# GabozeLite.net
KiCad netlist of a schematic drawn in EAGLE
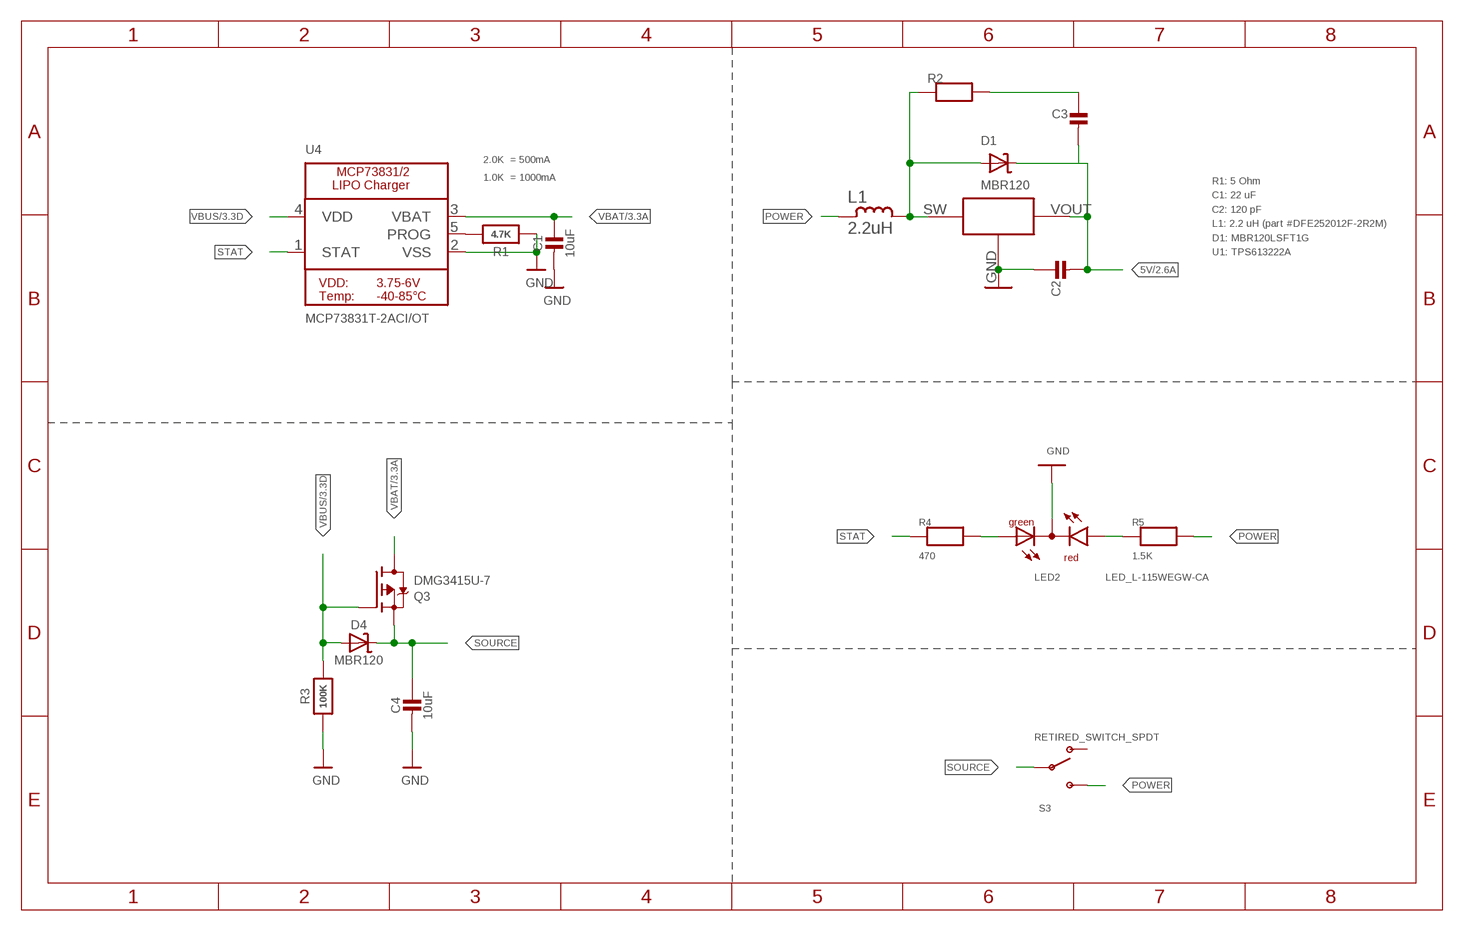
[diagram p0: schematic, sheet 1]
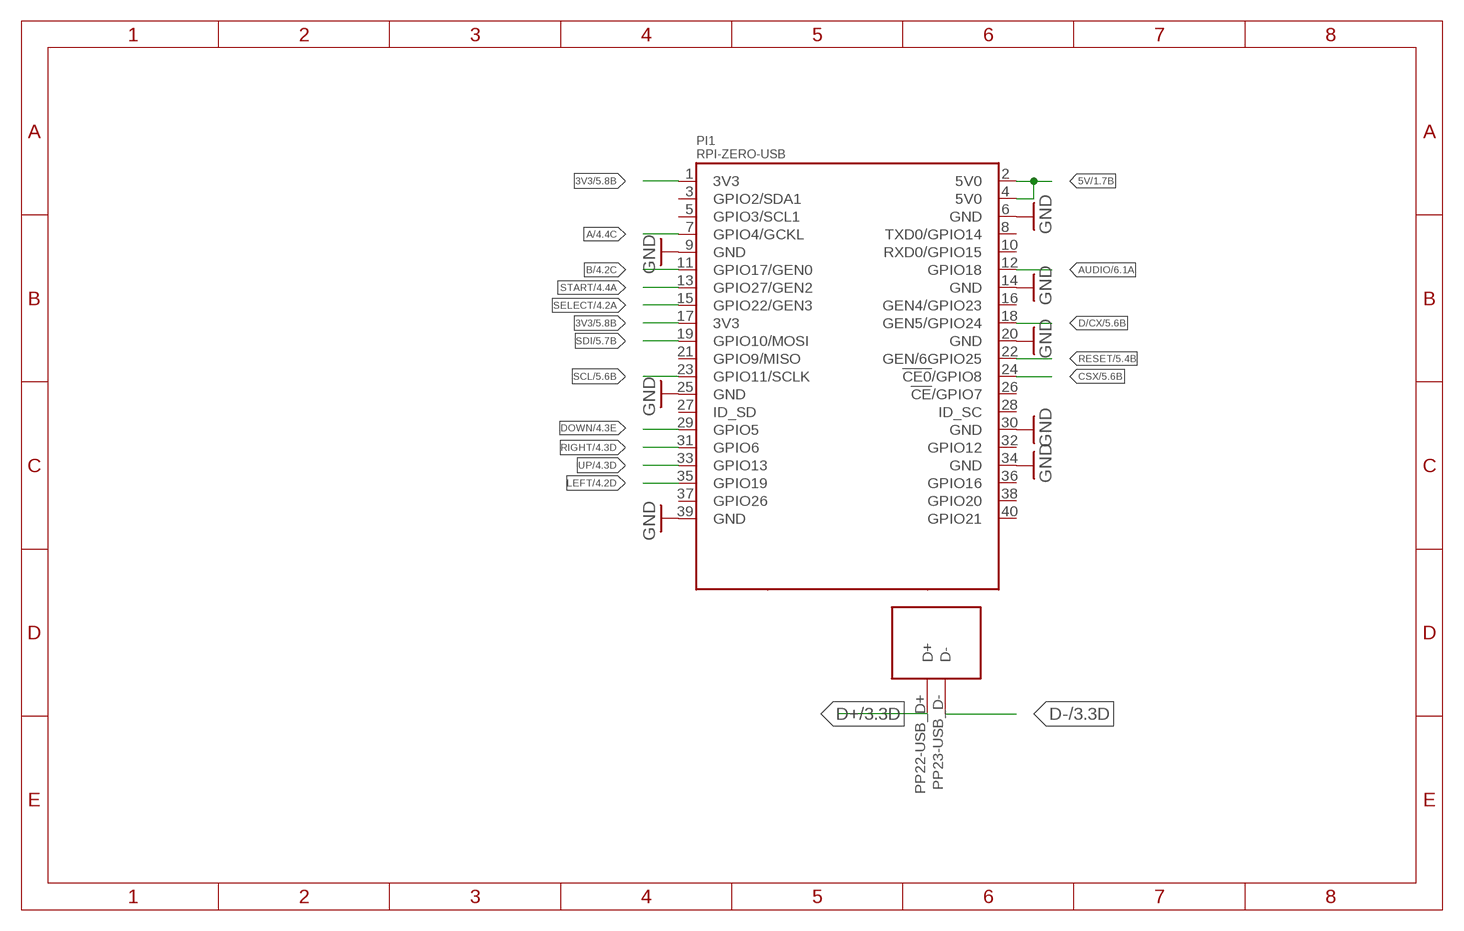
[diagram p1: schematic, sheet 2]
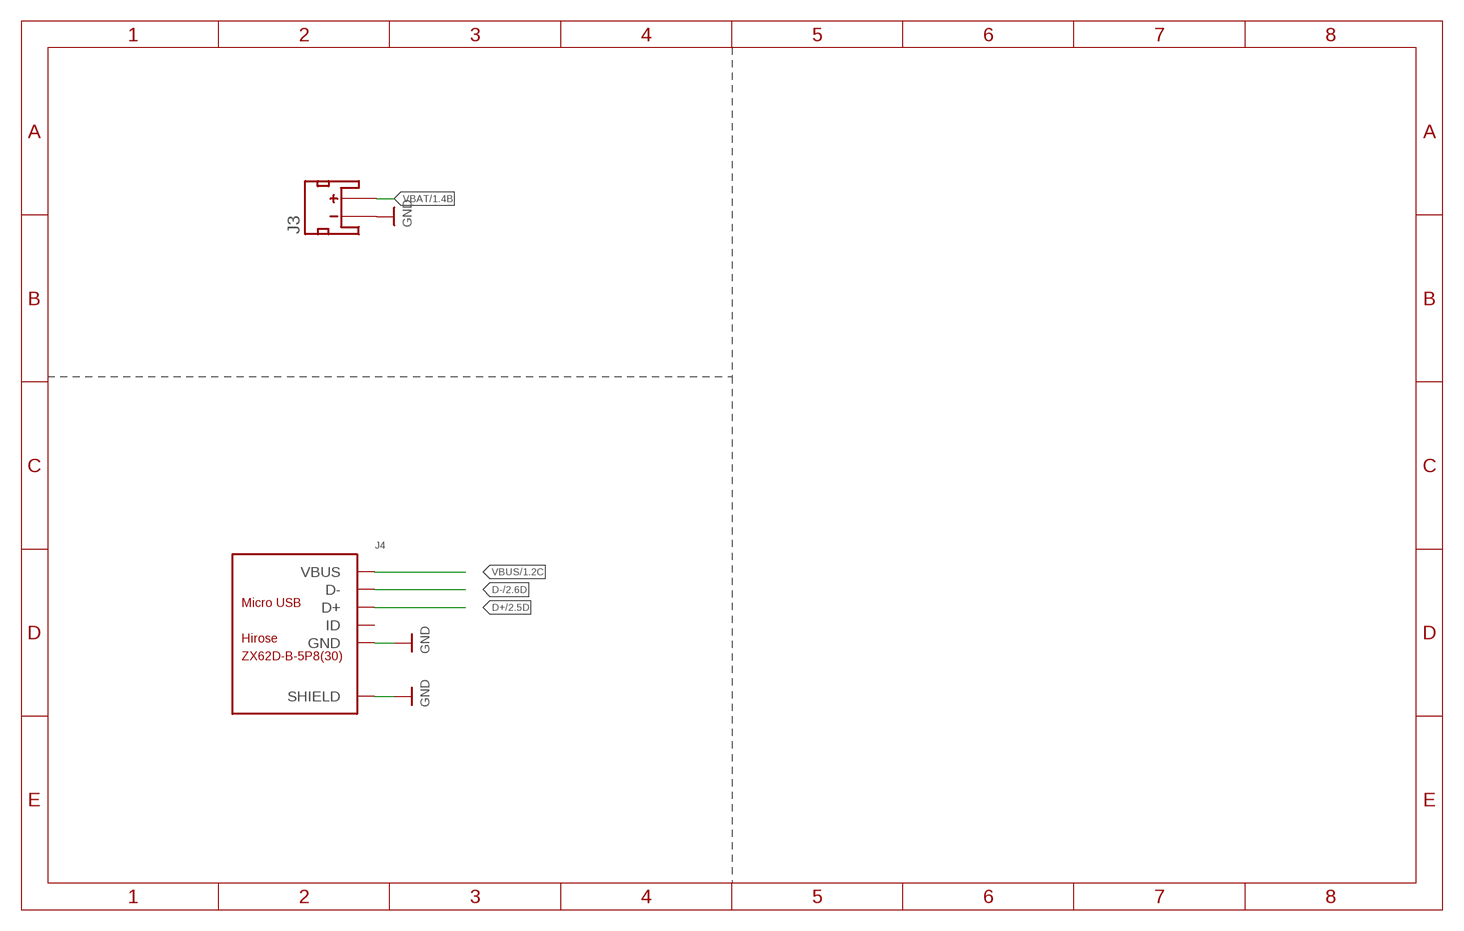
[diagram p2: schematic, sheet 3]
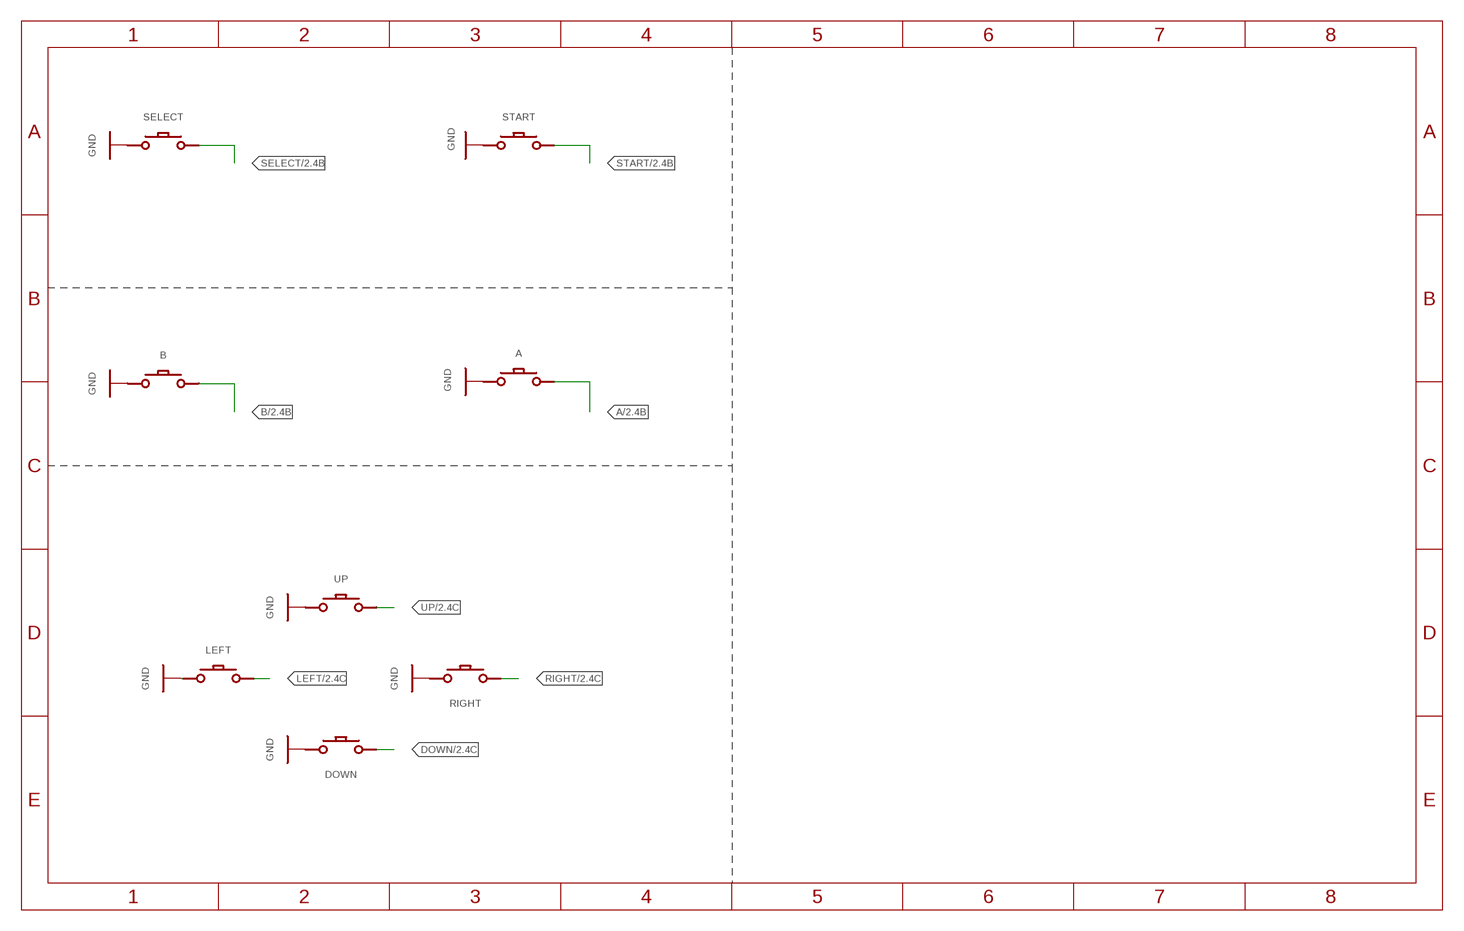
[diagram p3: schematic, sheet 4]
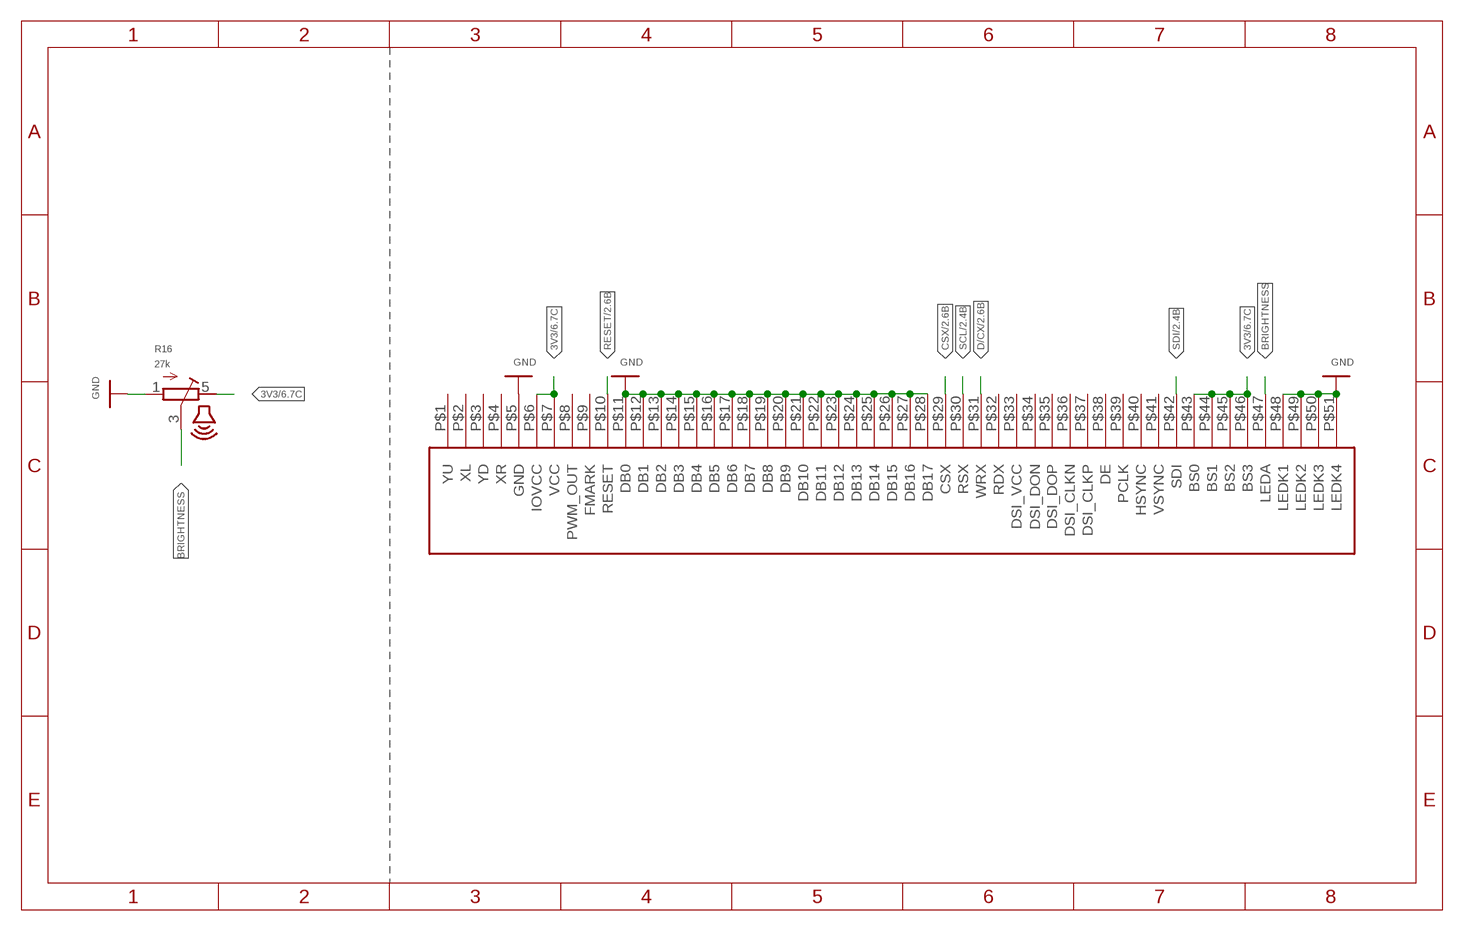
[diagram p4: schematic, sheet 5]
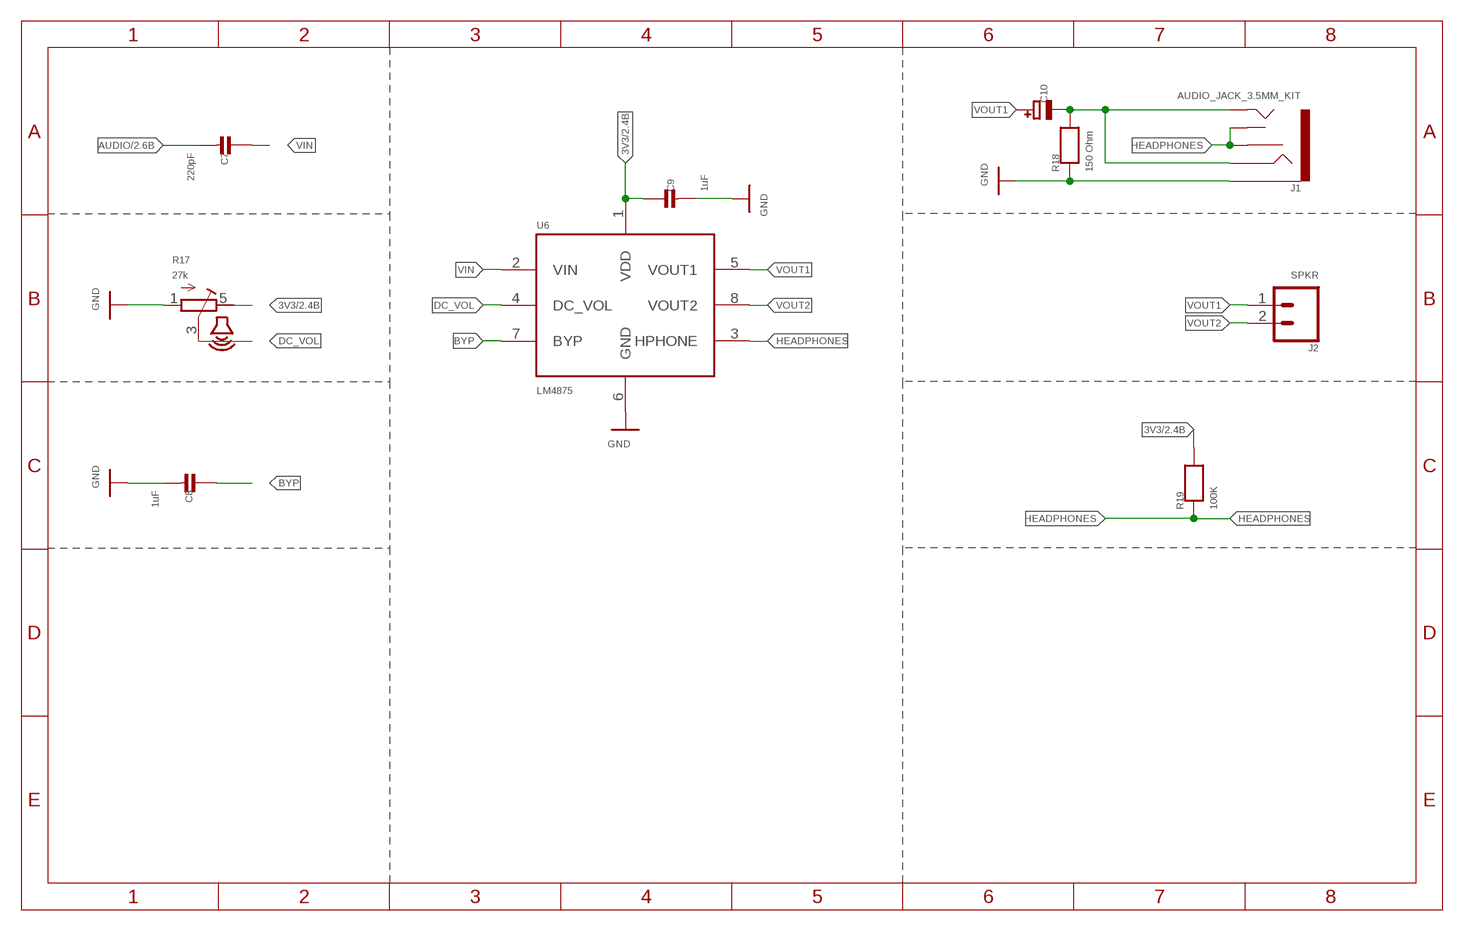
[diagram p5: schematic, sheet 6]
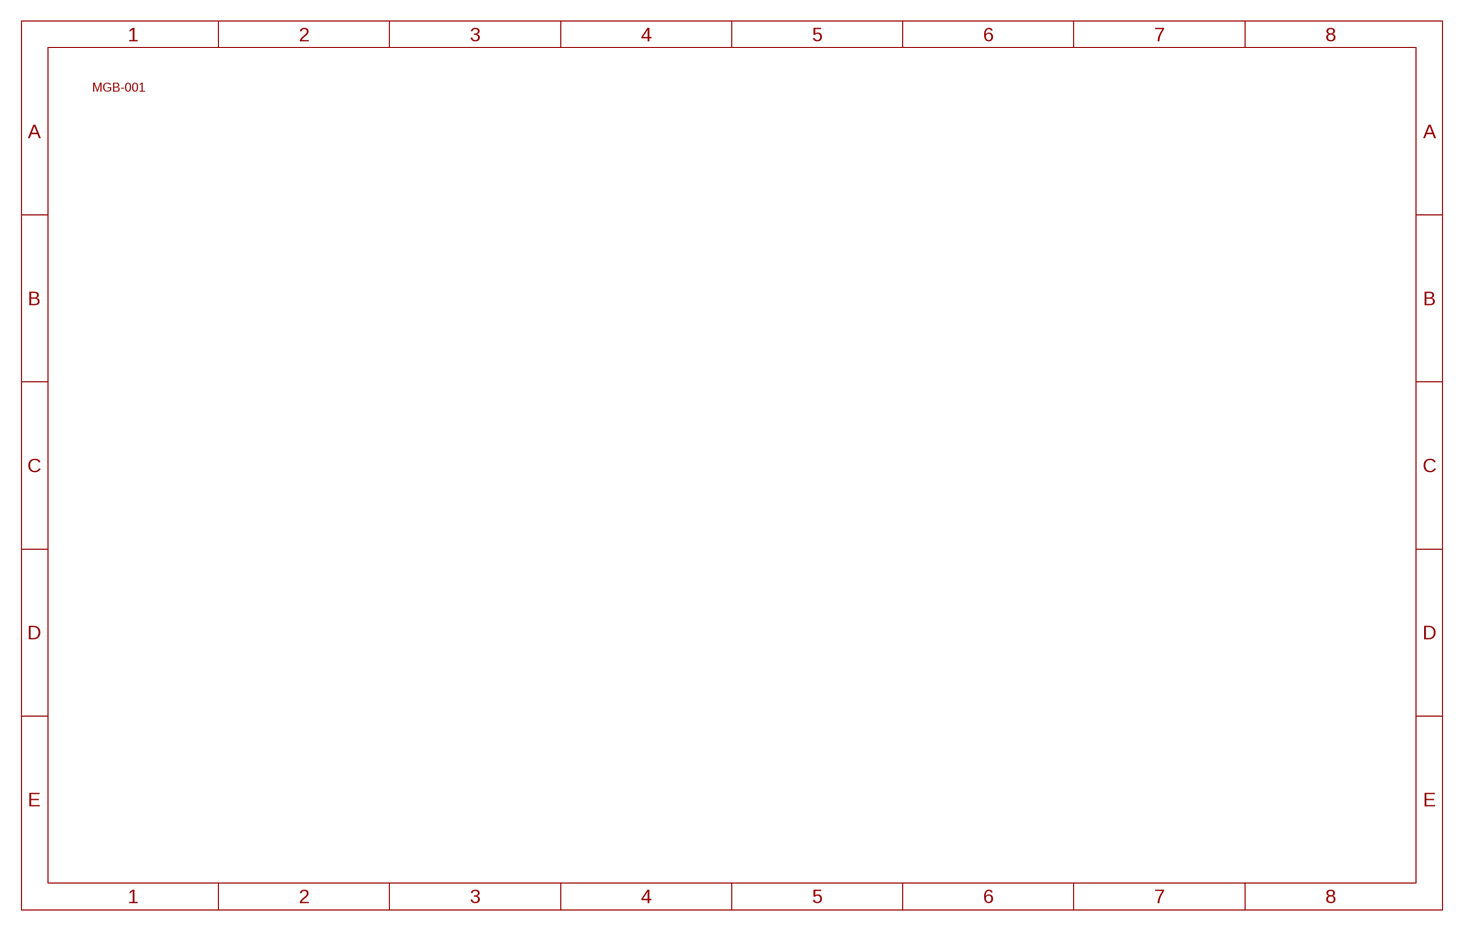
[diagram p6: schematic, sheet 7]

(export (version "E")
  (design (tool "Eeschema 10.0.6"))
  (components
    (comp (ref "C1")
      (value "10uF")
      (footprint "eagle-import:0603-MINI-CAP")
      (fields (field (name "MPN") "CL10A106MP8NNNC"))
      (libsource (lib "eagle-import") (part "CAP_CERAMIC"))
    )
    (comp (ref "C2")
      (value "22uf")
      (footprint "eagle-import:0603-MINI-CAP")
      (libsource (lib "eagle-import") (part "CAP_CERAMIC"))
    )
    (comp (ref "C3")
      (value "120pf")
      (footprint "eagle-import:0603-MINI-CAP")
      (libsource (lib "eagle-import") (part "CAP_CERAMIC"))
    )
    (comp (ref "C4")
      (value "10uF")
      (footprint "eagle-import:0603-MINI-CAP")
      (fields (field (name "MPN") "CL10A106MP8NNNC"))
      (libsource (lib "eagle-import") (part "CAP_CERAMIC"))
    )
    (comp (ref "D1")
      (value "MBR120")
      (footprint "eagle-import:SOD-123")
      (fields (field (name "MPN") "MBR120LSFT1G"))
      (libsource (lib "eagle-import") (part "DIODE-SCHOTTKYSOD-123"))
    )
    (comp (ref "D4")
      (value "MBR120")
      (footprint "eagle-import:SOD-123")
      (fields (field (name "MPN") "MBR120LSFT1G"))
      (libsource (lib "eagle-import") (part "DIODE-SCHOTTKYSOD-123"))
    )
    (comp (ref "L1")
      (value "2.2uH")
      (footprint "eagle-import:L1008CS")
      (libsource (lib "eagle-import") (part "L-1008CS"))
    )
    (comp (ref "LED2")
      (value "LED_L-115WEGW-CA")
      (footprint "eagle-import:LED_DUOLED-A-3MM")
      (fields (field (name "MPN") "SSL-LX3059IGW"))
      (libsource (lib "eagle-import") (part "LED_L-115WEGW-CA"))
    )
    (comp (ref "Q3")
      (value "DMG3415U-7")
      (footprint "eagle-import:SOT23-R")
      (libsource (lib "eagle-import") (part "MOSFET-P"))
    )
    (comp (ref "R1")
      (value "4.7K")
      (footprint "eagle-import:0603-MINI")
      (fields (field (name "MPN") "ERJ-PA3J472V"))
      (libsource (lib "eagle-import") (part "RESISTOR0603MINI"))
    )
    (comp (ref "R2")
      (value "5Ohm")
      (footprint "eagle-import:0603-MINI")
      (libsource (lib "eagle-import") (part "RESISTOR0603MINI"))
    )
    (comp (ref "R3")
      (value "100K")
      (footprint "eagle-import:0603-MINI")
      (fields (field (name "MPN") "ERJ-PA3J104V"))
      (libsource (lib "eagle-import") (part "RESISTOR0603MINI"))
    )
    (comp (ref "R4")
      (value "470")
      (footprint "eagle-import:0603-MINI")
      (fields (field (name "MPN") "ERJ-PA3J471V"))
      (libsource (lib "eagle-import") (part "RESISTOR0603MINI"))
    )
    (comp (ref "R5")
      (value "1.5K")
      (footprint "eagle-import:0603-MINI")
      (fields (field (name "MPN") "ERJ-PA3J152V"))
      (libsource (lib "eagle-import") (part "RESISTOR0603MINI"))
    )
    (comp (ref "S3")
      (value "RETIRED_SWITCH_SPDT")
      (footprint "eagle-import:RETIRED_KPS-1290")
      (fields (field (name "MPN") "RS-187R05A2-DS MT RT"))
      (libsource (lib "eagle-import") (part "RETIRED_SWITCH_SPDT"))
    )
    (comp (ref "U1")
      (value "TPS613222A")
      (footprint "eagle-import:TPS613222A")
      (libsource (lib "eagle-import") (part "TPS613222A"))
    )
    (comp (ref "U4")
      (value "MCP73831T-2ACI/OT")
      (footprint "eagle-import:SOT23-5-1")
      (libsource (lib "eagle-import") (part "MCP73831/2"))
    )
    (comp (ref "A")
      (value "CONDUCTIVE_BUTTONCONDUCTIVE_BUTTON_THICK")
      (footprint "eagle-import:CONDUCTIVE_BUTTON_THICK")
      (libsource (lib "eagle-import") (part "CONDUCTIVE_BUTTONCONDUCTIVE_BUTTON_THICK"))
    )
    (comp (ref "B")
      (value "CONDUCTIVE_BUTTONCONDUCTIVE_BUTTON_THICK")
      (footprint "eagle-import:CONDUCTIVE_BUTTON_THICK")
      (libsource (lib "eagle-import") (part "CONDUCTIVE_BUTTONCONDUCTIVE_BUTTON_THICK"))
    )
    (comp (ref "DOWN")
      (value "CONDUCTIVE_BUTTONCONDUCTIVE_BUTTON_DIRECTIONAL_THICK")
      (footprint "eagle-import:CONDUCTIVE_BUTTON_DIRECTIONAL_THICK")
      (libsource (lib "eagle-import") (part "CONDUCTIVE_BUTTONCONDUCTIVE_BUTTON_DIRECTIONAL_THICK"))
    )
    (comp (ref "LEFT")
      (value "CONDUCTIVE_BUTTONCONDUCTIVE_BUTTON_DIRECTIONAL_THICK")
      (footprint "eagle-import:CONDUCTIVE_BUTTON_DIRECTIONAL_THICK")
      (libsource (lib "eagle-import") (part "CONDUCTIVE_BUTTONCONDUCTIVE_BUTTON_DIRECTIONAL_THICK"))
    )
    (comp (ref "RIGHT")
      (value "CONDUCTIVE_BUTTONCONDUCTIVE_BUTTON_DIRECTIONAL_THICK")
      (footprint "eagle-import:CONDUCTIVE_BUTTON_DIRECTIONAL_THICK")
      (libsource (lib "eagle-import") (part "CONDUCTIVE_BUTTONCONDUCTIVE_BUTTON_DIRECTIONAL_THICK"))
    )
    (comp (ref "SELECT")
      (value "CONDUCTIVE_BUTTON_STARTSELECTCONDUCTIVE_BUTTON_THICK_STARTSELECT")
      (footprint "eagle-import:CONDUCTIVE_BUTTON_THICK_STARTSELECT")
      (libsource (lib "eagle-import") (part "CONDUCTIVE_BUTTON_STARTSELECTCONDUCTIVE_BUTTON_THICK_STARTSELECT"))
    )
    (comp (ref "START")
      (value "CONDUCTIVE_BUTTON_STARTSELECTCONDUCTIVE_BUTTON_THICK_STARTSELECT")
      (footprint "eagle-import:CONDUCTIVE_BUTTON_THICK_STARTSELECT")
      (libsource (lib "eagle-import") (part "CONDUCTIVE_BUTTON_STARTSELECTCONDUCTIVE_BUTTON_THICK_STARTSELECT"))
    )
    (comp (ref "UP")
      (value "CONDUCTIVE_BUTTONCONDUCTIVE_BUTTON_DIRECTIONAL_THICK")
      (footprint "eagle-import:CONDUCTIVE_BUTTON_DIRECTIONAL_THICK")
      (libsource (lib "eagle-import") (part "CONDUCTIVE_BUTTONCONDUCTIVE_BUTTON_DIRECTIONAL_THICK"))
    )
    (comp (ref "J3")
      (value "Batt Conn")
      (footprint "eagle-import:JST-2-SMD")
      (fields (field (name "MPN") "S2B-PH-SM4-TB(LF)(SN)"))
      (libsource (lib "eagle-import") (part "JST_2MM_MALE"))
    )
    (comp (ref "J4")
      (value "ZX62D-B-5P8(30)")
      (footprint "eagle-import:MICRO-USB5+6P-SMD-0.65-AB")
      (libsource (lib "eagle-import") (part "MICRO-USB-SMD(ZX62D-B-5P8(30))"))
    )
    (comp (ref "C7")
      (value "220pF")
      (footprint "eagle-import:0603-MINI-CAP")
      (fields (field (name "MPN") "CL10C221JB8NNNC"))
      (libsource (lib "eagle-import") (part "CAP_CERAMIC"))
    )
    (comp (ref "C8")
      (value "1uF")
      (footprint "eagle-import:0603-MINI-CAP")
      (fields (field (name "MPN") "CL10A105KP8NNNC"))
      (libsource (lib "eagle-import") (part "CAP_CERAMIC"))
    )
    (comp (ref "C9")
      (value "1uF")
      (footprint "eagle-import:0603-MINI-CAP")
      (fields (field (name "MPN") "CL10A105KP8NNNC"))
      (libsource (lib "eagle-import") (part "CAP_CERAMIC"))
    )
    (comp (ref "C10")
      (value "100uF")
      (footprint "eagle-import:EIA3216-18_A-W")
      (fields (field (name "MPN") "6TPH100MAEA"))
      (libsource (lib "eagle-import") (part "CAP_TANTALUMA/3216_WAVE"))
    )
    (comp (ref "J1")
      (value "AUDIO_JACK_3.5MM_KIT")
      (footprint "eagle-import:AUDIO-JACK-KIT")
      (fields (field (name "MPN") "SJ1-3525NG-GR"))
      (libsource (lib "eagle-import") (part "AUDIO_JACK_3.5MM_KIT"))
    )
    (comp (ref "J2")
      (value "SPKR")
      (footprint "eagle-import:1X02")
      (libsource (lib "eagle-import") (part "CONN_02"))
    )
    (comp (ref "R17")
      (value "27k")
      (footprint "eagle-import:THUMBWHEEL")
      (libsource (lib "eagle-import") (part "THUMBWHEEL"))
    )
    (comp (ref "R18")
      (value "150 Ohm")
      (footprint "eagle-import:0603-MINI")
      (fields (field (name "MPN") "ERJ-PA3J151V"))
      (libsource (lib "eagle-import") (part "RESISTOR0603MINI"))
    )
    (comp (ref "R19")
      (value "100K")
      (footprint "eagle-import:0603-MINI")
      (fields (field (name "MPN") "ERJ-PA3J104V"))
      (libsource (lib "eagle-import") (part "RESISTOR0603MINI"))
    )
    (comp (ref "U6")
      (value "LM4875")
      (footprint "eagle-import:SOIC8")
      (fields (field (name "MPN") "LM4875M/NOPB"))
      (libsource (lib "eagle-import") (part "LM4875"))
    )
    (comp (ref "R16")
      (value "27k")
      (footprint "eagle-import:THUMBWHEEL")
      (libsource (lib "eagle-import") (part "THUMBWHEEL"))
    )
    (comp (ref "U5")
      (value "ILI9342-2.6\"")
      (footprint "eagle-import:ILI9342-2.6_")
      (libsource (lib "eagle-import") (part "ILI9342-2.6{dblquote}"))
    )
    (comp (ref "U$1")
      (value "MGB-001")
      (footprint "eagle-import:MGB-001")
      (libsource (lib "eagle-import") (part "MGB-001"))
    )
    (comp (ref "PI1")
      (value "RPI-ZERO-USB")
      (footprint "eagle-import:RPI-ZERO-TH-USB-POGO")
      (libsource (lib "eagle-import") (part "RPI-ZERO-USB"))
    )
  )
  (nets
    (net (code "1") (name "3V3") (class "Default")
      (node (ref "C9") (pin "1") (pinfunction "1_1") (pintype "passive"))
      (node (ref "PI1") (pin "1") (pinfunction "3V3_1") (pintype "power_in"))
      (node (ref "PI1") (pin "17") (pinfunction "3V3_17") (pintype "power_in"))
      (node (ref "R16") (pin "5") (pinfunction "E_5") (pintype "passive"))
      (node (ref "R17") (pin "5") (pinfunction "E_5") (pintype "passive"))
      (node (ref "R19") (pin "2") (pinfunction "2_2") (pintype "passive"))
      (node (ref "U5") (pin "P$43") (pinfunction "BS0_P$43") (pintype "bidirectional"))
      (node (ref "U5") (pin "P$44") (pinfunction "BS1_P$44") (pintype "bidirectional"))
      (node (ref "U5") (pin "P$45") (pinfunction "BS2_P$45") (pintype "bidirectional"))
      (node (ref "U5") (pin "P$46") (pinfunction "BS3_P$46") (pintype "bidirectional"))
      (node (ref "U5") (pin "P$6") (pinfunction "IOVCC_P$6") (pintype "bidirectional"))
      (node (ref "U5") (pin "P$7") (pinfunction "VCC_P$7") (pintype "bidirectional"))
      (node (ref "U6") (pin "1") (pinfunction "VDD_1") (pintype "power_in"))
    )
    (net (code "2") (name "5V") (class "Default")
      (node (ref "C2") (pin "2") (pinfunction "2_2") (pintype "passive"))
      (node (ref "C3") (pin "2") (pinfunction "2_2") (pintype "passive"))
      (node (ref "D1") (pin "C") (pinfunction "C_C") (pintype "passive"))
      (node (ref "PI1") (pin "2") (pinfunction "5V0_2") (pintype "power_in"))
      (node (ref "PI1") (pin "4") (pinfunction "5V0_4") (pintype "power_in"))
      (node (ref "U1") (pin "VOUT") (pinfunction "VOUT_VOUT") (pintype "bidirectional"))
    )
    (net (code "3") (name "A") (class "Default")
      (node (ref "A") (pin "P$ACTIVE") (pinfunction "P$ACTIVE_P$ACTIVE") (pintype "bidirectional"))
      (node (ref "PI1") (pin "7") (pinfunction "GPIO4/GCKL_7") (pintype "bidirectional"))
    )
    (net (code "4") (name "AUDIO") (class "Default")
      (node (ref "C7") (pin "2") (pinfunction "2_2") (pintype "passive"))
      (node (ref "PI1") (pin "12") (pinfunction "GPIO18_12") (pintype "bidirectional"))
    )
    (net (code "5") (name "B") (class "Default")
      (node (ref "B") (pin "P$ACTIVE") (pinfunction "P$ACTIVE_P$ACTIVE") (pintype "bidirectional"))
      (node (ref "PI1") (pin "11") (pinfunction "GPIO17/GEN0_11") (pintype "bidirectional"))
    )
    (net (code "6") (name "BRIGHTNESS") (class "Default")
      (node (ref "R16") (pin "3") (pinfunction "S_3") (pintype "passive"))
      (node (ref "U5") (pin "P$47") (pinfunction "LEDA_P$47") (pintype "bidirectional"))
    )
    (net (code "7") (name "BYP") (class "Default")
      (node (ref "C8") (pin "1") (pinfunction "1_1") (pintype "passive"))
      (node (ref "U6") (pin "7") (pinfunction "BYP_7") (pintype "bidirectional"))
    )
    (net (code "8") (name "CSX") (class "Default")
      (node (ref "PI1") (pin "24") (pinfunction "~{CE0}/GPIO8_24") (pintype "bidirectional"))
      (node (ref "U5") (pin "P$29") (pinfunction "CSX_P$29") (pintype "bidirectional"))
    )
    (net (code "9") (name "D+") (class "Default")
      (node (ref "J4") (pin "3") (pinfunction "D+_3") (pintype "bidirectional"))
      (node (ref "PI1") (pin "PP22-USB_D+") (pinfunction "D+_PP22-USB_D+") (pintype "bidirectional"))
    )
    (net (code "10") (name "D-") (class "Default")
      (node (ref "J4") (pin "2") (pinfunction "D-_2") (pintype "bidirectional"))
      (node (ref "PI1") (pin "PP23-USB_D-") (pinfunction "D-_PP23-USB_D-") (pintype "bidirectional"))
    )
    (net (code "11") (name "DC_VOL") (class "Default")
      (node (ref "R17") (pin "3") (pinfunction "S_3") (pintype "passive"))
      (node (ref "U6") (pin "4") (pinfunction "DC_VOL_4") (pintype "input"))
    )
    (net (code "12") (name "DOWN") (class "Default")
      (node (ref "DOWN") (pin "P$ACTIVE") (pinfunction "P$ACTIVE_P$ACTIVE") (pintype "bidirectional"))
      (node (ref "PI1") (pin "29") (pinfunction "GPIO5_29") (pintype "bidirectional"))
    )
    (net (code "13") (name "D{slash}CX") (class "Default")
      (node (ref "PI1") (pin "18") (pinfunction "GEN5/GPIO24_18") (pintype "bidirectional"))
      (node (ref "U5") (pin "P$31") (pinfunction "WRX_P$31") (pintype "bidirectional"))
    )
    (net (code "14") (name "GND") (class "Default")
      (node (ref "A") (pin "P$GND") (pinfunction "P$GND_P$GND") (pintype "bidirectional"))
      (node (ref "B") (pin "P$GND") (pinfunction "P$GND_P$GND") (pintype "bidirectional"))
      (node (ref "C1") (pin "2") (pinfunction "2_2") (pintype "passive"))
      (node (ref "C2") (pin "1") (pinfunction "1_1") (pintype "passive"))
      (node (ref "C4") (pin "2") (pinfunction "2_2") (pintype "passive"))
      (node (ref "C8") (pin "2") (pinfunction "2_2") (pintype "passive"))
      (node (ref "C9") (pin "2") (pinfunction "2_2") (pintype "passive"))
      (node (ref "DOWN") (pin "P$GND") (pinfunction "P$GND_P$GND") (pintype "bidirectional"))
      (node (ref "J1") (pin "SLEEVE") (pinfunction "SLEEVE_SLEEVE") (pintype "bidirectional"))
      (node (ref "J3") (pin "1") (pinfunction "-_1") (pintype "bidirectional"))
      (node (ref "J4") (pin "5") (pinfunction "GND_5") (pintype "power_in"))
      (node (ref "J4") (pin "P1") (pinfunction "SHIELD_P1") (pintype "power_in"))
      (node (ref "J4") (pin "P2") (pinfunction "SHIELD_P2") (pintype "power_in"))
      (node (ref "J4") (pin "P3") (pinfunction "SHIELD_P3") (pintype "power_in"))
      (node (ref "J4") (pin "P4") (pinfunction "SHIELD_P4") (pintype "power_in"))
      (node (ref "J4") (pin "P5") (pinfunction "SHIELD_P5") (pintype "power_in"))
      (node (ref "J4") (pin "P6") (pinfunction "SHIELD_P6") (pintype "power_in"))
      (node (ref "LED2") (pin "2") (pinfunction "A_2") (pintype "passive"))
      (node (ref "LEFT") (pin "P$GND") (pinfunction "P$GND_P$GND") (pintype "bidirectional"))
      (node (ref "PI1") (pin "14") (pinfunction "GND_14") (pintype "power_in"))
      (node (ref "PI1") (pin "20") (pinfunction "GND_20") (pintype "power_in"))
      (node (ref "PI1") (pin "25") (pinfunction "GND_25") (pintype "power_in"))
      (node (ref "PI1") (pin "30") (pinfunction "GND_30") (pintype "power_in"))
      (node (ref "PI1") (pin "34") (pinfunction "GND_34") (pintype "power_in"))
      (node (ref "PI1") (pin "39") (pinfunction "GND_39") (pintype "power_in"))
      (node (ref "PI1") (pin "6") (pinfunction "GND_6") (pintype "power_in"))
      (node (ref "PI1") (pin "9") (pinfunction "GND_9") (pintype "power_in"))
      (node (ref "R1") (pin "1") (pinfunction "1_1") (pintype "passive"))
      (node (ref "R16") (pin "1") (pinfunction "A_1") (pintype "passive"))
      (node (ref "R17") (pin "1") (pinfunction "A_1") (pintype "passive"))
      (node (ref "R18") (pin "1") (pinfunction "1_1") (pintype "passive"))
      (node (ref "R3") (pin "1") (pinfunction "1_1") (pintype "passive"))
      (node (ref "RIGHT") (pin "P$GND") (pinfunction "P$GND_P$GND") (pintype "bidirectional"))
      (node (ref "SELECT") (pin "P$GND") (pinfunction "P$GND_P$GND") (pintype "bidirectional"))
      (node (ref "SELECT") (pin "P$GND1") (pinfunction "P$GND_P$GND1") (pintype "bidirectional"))
      (node (ref "SELECT") (pin "P$GND2") (pinfunction "P$GND_P$GND2") (pintype "bidirectional"))
      (node (ref "SELECT") (pin "P$GND3") (pinfunction "P$GND_P$GND3") (pintype "bidirectional"))
      (node (ref "START") (pin "P$GND") (pinfunction "P$GND_P$GND") (pintype "bidirectional"))
      (node (ref "START") (pin "P$GND1") (pinfunction "P$GND_P$GND1") (pintype "bidirectional"))
      (node (ref "START") (pin "P$GND2") (pinfunction "P$GND_P$GND2") (pintype "bidirectional"))
      (node (ref "START") (pin "P$GND3") (pinfunction "P$GND_P$GND3") (pintype "bidirectional"))
      (node (ref "U1") (pin "GND") (pinfunction "GND_GND") (pintype "bidirectional"))
      (node (ref "U4") (pin "2") (pinfunction "VSS_2") (pintype "power_in"))
      (node (ref "U5") (pin "P$11") (pinfunction "DB0_P$11") (pintype "bidirectional"))
      (node (ref "U5") (pin "P$12") (pinfunction "DB1_P$12") (pintype "bidirectional"))
      (node (ref "U5") (pin "P$13") (pinfunction "DB2_P$13") (pintype "bidirectional"))
      (node (ref "U5") (pin "P$14") (pinfunction "DB3_P$14") (pintype "bidirectional"))
      (node (ref "U5") (pin "P$15") (pinfunction "DB4_P$15") (pintype "bidirectional"))
      (node (ref "U5") (pin "P$16") (pinfunction "DB5_P$16") (pintype "bidirectional"))
      (node (ref "U5") (pin "P$17") (pinfunction "DB6_P$17") (pintype "bidirectional"))
      (node (ref "U5") (pin "P$18") (pinfunction "DB7_P$18") (pintype "bidirectional"))
      (node (ref "U5") (pin "P$19") (pinfunction "DB8_P$19") (pintype "bidirectional"))
      (node (ref "U5") (pin "P$20") (pinfunction "DB9_P$20") (pintype "bidirectional"))
      (node (ref "U5") (pin "P$21") (pinfunction "DB10_P$21") (pintype "bidirectional"))
      (node (ref "U5") (pin "P$22") (pinfunction "DB11_P$22") (pintype "bidirectional"))
      (node (ref "U5") (pin "P$23") (pinfunction "DB12_P$23") (pintype "bidirectional"))
      (node (ref "U5") (pin "P$24") (pinfunction "DB13_P$24") (pintype "bidirectional"))
      (node (ref "U5") (pin "P$25") (pinfunction "DB14_P$25") (pintype "bidirectional"))
      (node (ref "U5") (pin "P$26") (pinfunction "DB15_P$26") (pintype "bidirectional"))
      (node (ref "U5") (pin "P$27") (pinfunction "DB16_P$27") (pintype "bidirectional"))
      (node (ref "U5") (pin "P$28") (pinfunction "DB17_P$28") (pintype "bidirectional"))
      (node (ref "U5") (pin "P$48") (pinfunction "LEDK1_P$48") (pintype "bidirectional"))
      (node (ref "U5") (pin "P$49") (pinfunction "LEDK2_P$49") (pintype "bidirectional"))
      (node (ref "U5") (pin "P$5") (pinfunction "GND_P$5") (pintype "bidirectional"))
      (node (ref "U5") (pin "P$50") (pinfunction "LEDK3_P$50") (pintype "bidirectional"))
      (node (ref "U5") (pin "P$51") (pinfunction "LEDK4_P$51") (pintype "bidirectional"))
      (node (ref "U6") (pin "6") (pinfunction "GND_6") (pintype "power_in"))
      (node (ref "UP") (pin "P$GND") (pinfunction "P$GND_P$GND") (pintype "bidirectional"))
    )
    (net (code "15") (name "HEADPHONES") (class "Default")
      (node (ref "J1") (pin "RSH") (pinfunction "RSH_RSH") (pintype "bidirectional"))
      (node (ref "J1") (pin "TSH") (pinfunction "TSH_TSH") (pintype "bidirectional"))
      (node (ref "R19") (pin "1") (pinfunction "1_1") (pintype "passive"))
      (node (ref "U6") (pin "3") (pinfunction "HPHONE_3") (pintype "input"))
    )
    (net (code "16") (name "LEFT") (class "Default")
      (node (ref "LEFT") (pin "P$ACTIVE") (pinfunction "P$ACTIVE_P$ACTIVE") (pintype "bidirectional"))
      (node (ref "PI1") (pin "35") (pinfunction "GPIO19_35") (pintype "bidirectional"))
    )
    (net (code "17") (name "Net-(C3-Pad1)") (class "Default")
      (node (ref "C3") (pin "1") (pinfunction "1_1") (pintype "passive"))
      (node (ref "R2") (pin "2") (pinfunction "2_2") (pintype "passive"))
    )
    (net (code "18") (name "Net-(C10-Pad-)") (class "Default")
      (node (ref "C10") (pin "-") (pinfunction "-_-") (pintype "passive"))
      (node (ref "J1") (pin "RING") (pinfunction "RING_RING") (pintype "bidirectional"))
      (node (ref "J1") (pin "TIP") (pinfunction "TIP_TIP") (pintype "bidirectional"))
      (node (ref "R18") (pin "2") (pinfunction "2_2") (pintype "passive"))
    )
    (net (code "19") (name "Net-(L1-P$2)") (class "Default")
      (node (ref "D1") (pin "A") (pinfunction "A_A") (pintype "passive"))
      (node (ref "L1") (pin "2") (pinfunction "P$2_2") (pintype "passive"))
      (node (ref "R2") (pin "1") (pinfunction "1_1") (pintype "passive"))
      (node (ref "U1") (pin "SW") (pinfunction "SW_SW") (pintype "bidirectional"))
    )
    (net (code "20") (name "Net-(LED2-CG)") (class "Default")
      (node (ref "LED2") (pin "1") (pinfunction "CG_1") (pintype "passive"))
      (node (ref "R4") (pin "2") (pinfunction "2_2") (pintype "passive"))
    )
    (net (code "21") (name "Net-(LED2-CR)") (class "Default")
      (node (ref "LED2") (pin "3") (pinfunction "CR_3") (pintype "passive"))
      (node (ref "R5") (pin "1") (pinfunction "1_1") (pintype "passive"))
    )
    (net (code "22") (name "Net-(U4-PROG)") (class "Default")
      (node (ref "R1") (pin "2") (pinfunction "2_2") (pintype "passive"))
      (node (ref "U4") (pin "5") (pinfunction "PROG_5") (pintype "input"))
    )
    (net (code "23") (name "POWER") (class "Default")
      (node (ref "L1") (pin "1") (pinfunction "P$1_1") (pintype "passive"))
      (node (ref "R5") (pin "2") (pinfunction "2_2") (pintype "passive"))
      (node (ref "S3") (pin "S") (pinfunction "S_S") (pintype "passive"))
    )
    (net (code "24") (name "RESET") (class "Default")
      (node (ref "PI1") (pin "22") (pinfunction "GEN/6GPIO25_22") (pintype "bidirectional"))
      (node (ref "U5") (pin "P$10") (pinfunction "RESET_P$10") (pintype "bidirectional"))
    )
    (net (code "25") (name "RIGHT") (class "Default")
      (node (ref "PI1") (pin "31") (pinfunction "GPIO6_31") (pintype "bidirectional"))
      (node (ref "RIGHT") (pin "P$ACTIVE") (pinfunction "P$ACTIVE_P$ACTIVE") (pintype "bidirectional"))
    )
    (net (code "26") (name "SCL") (class "Default")
      (node (ref "PI1") (pin "23") (pinfunction "GPIO11/SCLK_23") (pintype "bidirectional"))
      (node (ref "U5") (pin "P$30") (pinfunction "RSX_P$30") (pintype "bidirectional"))
    )
    (net (code "27") (name "SDI") (class "Default")
      (node (ref "PI1") (pin "19") (pinfunction "GPIO10/MOSI_19") (pintype "bidirectional"))
      (node (ref "U5") (pin "P$42") (pinfunction "SDI_P$42") (pintype "bidirectional"))
    )
    (net (code "28") (name "SELECT") (class "Default")
      (node (ref "PI1") (pin "15") (pinfunction "GPIO22/GEN3_15") (pintype "bidirectional"))
      (node (ref "SELECT") (pin "P$ACTIVE") (pinfunction "P$ACTIVE_P$ACTIVE") (pintype "bidirectional"))
      (node (ref "SELECT") (pin "P$ACTIVE1") (pinfunction "P$ACTIVE_P$ACTIVE1") (pintype "bidirectional"))
      (node (ref "SELECT") (pin "P$ACTIVE2") (pinfunction "P$ACTIVE_P$ACTIVE2") (pintype "bidirectional"))
      (node (ref "SELECT") (pin "P$ACTIVE3") (pinfunction "P$ACTIVE_P$ACTIVE3") (pintype "bidirectional"))
      (node (ref "SELECT") (pin "P$ACTIVE4") (pinfunction "P$ACTIVE_P$ACTIVE4") (pintype "bidirectional"))
      (node (ref "SELECT") (pin "P$ACTIVE5") (pinfunction "P$ACTIVE_P$ACTIVE5") (pintype "bidirectional"))
      (node (ref "SELECT") (pin "P$ACTIVE6") (pinfunction "P$ACTIVE_P$ACTIVE6") (pintype "bidirectional"))
    )
    (net (code "29") (name "SOURCE") (class "Default")
      (node (ref "C4") (pin "1") (pinfunction "1_1") (pintype "passive"))
      (node (ref "D4") (pin "C") (pinfunction "C_C") (pintype "passive"))
      (node (ref "Q3") (pin "2") (pinfunction "S_2") (pintype "passive"))
      (node (ref "S3") (pin "P") (pinfunction "P_P") (pintype "passive"))
    )
    (net (code "30") (name "START") (class "Default")
      (node (ref "PI1") (pin "13") (pinfunction "GPIO27/GEN2_13") (pintype "bidirectional"))
      (node (ref "START") (pin "P$ACTIVE") (pinfunction "P$ACTIVE_P$ACTIVE") (pintype "bidirectional"))
      (node (ref "START") (pin "P$ACTIVE1") (pinfunction "P$ACTIVE_P$ACTIVE1") (pintype "bidirectional"))
      (node (ref "START") (pin "P$ACTIVE2") (pinfunction "P$ACTIVE_P$ACTIVE2") (pintype "bidirectional"))
      (node (ref "START") (pin "P$ACTIVE3") (pinfunction "P$ACTIVE_P$ACTIVE3") (pintype "bidirectional"))
      (node (ref "START") (pin "P$ACTIVE4") (pinfunction "P$ACTIVE_P$ACTIVE4") (pintype "bidirectional"))
      (node (ref "START") (pin "P$ACTIVE5") (pinfunction "P$ACTIVE_P$ACTIVE5") (pintype "bidirectional"))
      (node (ref "START") (pin "P$ACTIVE6") (pinfunction "P$ACTIVE_P$ACTIVE6") (pintype "bidirectional"))
    )
    (net (code "31") (name "STAT") (class "Default")
      (node (ref "R4") (pin "1") (pinfunction "1_1") (pintype "passive"))
      (node (ref "U4") (pin "1") (pinfunction "STAT_1") (pintype "output"))
    )
    (net (code "32") (name "UP") (class "Default")
      (node (ref "PI1") (pin "33") (pinfunction "GPIO13_33") (pintype "bidirectional"))
      (node (ref "UP") (pin "P$ACTIVE") (pinfunction "P$ACTIVE_P$ACTIVE") (pintype "bidirectional"))
    )
    (net (code "33") (name "VBAT") (class "Default")
      (node (ref "C1") (pin "1") (pinfunction "1_1") (pintype "passive"))
      (node (ref "J3") (pin "2") (pinfunction "+_2") (pintype "bidirectional"))
      (node (ref "Q3") (pin "3") (pinfunction "D_3") (pintype "passive"))
      (node (ref "U4") (pin "3") (pinfunction "VBAT_3") (pintype "power_in"))
    )
    (net (code "34") (name "VBUS") (class "Default")
      (node (ref "D4") (pin "A") (pinfunction "A_A") (pintype "passive"))
      (node (ref "J4") (pin "1") (pinfunction "VBUS_1") (pintype "power_in"))
      (node (ref "Q3") (pin "1") (pinfunction "G_1") (pintype "passive"))
      (node (ref "R3") (pin "2") (pinfunction "2_2") (pintype "passive"))
      (node (ref "U4") (pin "4") (pinfunction "VDD_4") (pintype "power_in"))
    )
    (net (code "35") (name "VIN") (class "Default")
      (node (ref "C7") (pin "1") (pinfunction "1_1") (pintype "passive"))
      (node (ref "U6") (pin "2") (pinfunction "VIN_2") (pintype "input"))
    )
    (net (code "36") (name "VOUT1") (class "Default")
      (node (ref "C10") (pin "+") (pinfunction "+_+") (pintype "passive"))
      (node (ref "J2") (pin "1") (pinfunction "1_1") (pintype "passive"))
      (node (ref "U6") (pin "5") (pinfunction "VOUT1_5") (pintype "output"))
    )
    (net (code "37") (name "VOUT2") (class "Default")
      (node (ref "J2") (pin "2") (pinfunction "2_2") (pintype "passive"))
      (node (ref "U6") (pin "8") (pinfunction "VOUT2_8") (pintype "output"))
    )
    (net (code "38") (name "unconnected-(J3-PAD1-PadNC1)") (class "Default")
      (node (ref "J3") (pin "NC1") (pinfunction "PAD1_NC1") (pintype "bidirectional"))
    )
    (net (code "39") (name "unconnected-(J3-PAD2-PadNC2)") (class "Default")
      (node (ref "J3") (pin "NC2") (pinfunction "PAD2_NC2") (pintype "bidirectional"))
    )
    (net (code "40") (name "unconnected-(J4-ID-Pad4)") (class "Default")
      (node (ref "J4") (pin "4") (pinfunction "ID_4") (pintype "bidirectional"))
    )
    (net (code "41") (name "unconnected-(PI1-GEN4{slash}GPIO23-Pad16)") (class "Default")
      (node (ref "PI1") (pin "16") (pinfunction "GEN4/GPIO23_16") (pintype "bidirectional"))
    )
    (net (code "42") (name "unconnected-(PI1-GPIO2{slash}SDA1-Pad3)") (class "Default")
      (node (ref "PI1") (pin "3") (pinfunction "GPIO2/SDA1_3") (pintype "bidirectional"))
    )
    (net (code "43") (name "unconnected-(PI1-GPIO3{slash}SCL1-Pad5)") (class "Default")
      (node (ref "PI1") (pin "5") (pinfunction "GPIO3/SCL1_5") (pintype "bidirectional"))
    )
    (net (code "44") (name "unconnected-(PI1-GPIO9{slash}MISO-Pad21)") (class "Default")
      (node (ref "PI1") (pin "21") (pinfunction "GPIO9/MISO_21") (pintype "bidirectional"))
    )
    (net (code "45") (name "unconnected-(PI1-GPIO12-Pad32)") (class "Default")
      (node (ref "PI1") (pin "32") (pinfunction "GPIO12_32") (pintype "bidirectional"))
    )
    (net (code "46") (name "unconnected-(PI1-GPIO16-Pad36)") (class "Default")
      (node (ref "PI1") (pin "36") (pinfunction "GPIO16_36") (pintype "bidirectional"))
    )
    (net (code "47") (name "unconnected-(PI1-GPIO20-Pad38)") (class "Default")
      (node (ref "PI1") (pin "38") (pinfunction "GPIO20_38") (pintype "bidirectional"))
    )
    (net (code "48") (name "unconnected-(PI1-GPIO21-Pad40)") (class "Default")
      (node (ref "PI1") (pin "40") (pinfunction "GPIO21_40") (pintype "bidirectional"))
    )
    (net (code "49") (name "unconnected-(PI1-GPIO26-Pad37)") (class "Default")
      (node (ref "PI1") (pin "37") (pinfunction "GPIO26_37") (pintype "bidirectional"))
    )
    (net (code "50") (name "unconnected-(PI1-ID_SC-Pad28)") (class "Default")
      (node (ref "PI1") (pin "28") (pinfunction "ID_SC_28") (pintype "bidirectional"))
    )
    (net (code "51") (name "unconnected-(PI1-ID_SD-Pad27)") (class "Default")
      (node (ref "PI1") (pin "27") (pinfunction "ID_SD_27") (pintype "bidirectional"))
    )
    (net (code "52") (name "unconnected-(PI1-RXD0{slash}GPIO15-Pad10)") (class "Default")
      (node (ref "PI1") (pin "10") (pinfunction "RXD0/GPIO15_10") (pintype "bidirectional"))
    )
    (net (code "53") (name "unconnected-(PI1-TXD0{slash}GPIO14-Pad8)") (class "Default")
      (node (ref "PI1") (pin "8") (pinfunction "TXD0/GPIO14_8") (pintype "bidirectional"))
    )
    (net (code "54") (name "unconnected-(PI1-~{CE}{slash}GPIO7-Pad26)") (class "Default")
      (node (ref "PI1") (pin "26") (pinfunction "~{CE}/GPIO7_26") (pintype "bidirectional"))
    )
    (net (code "55") (name "unconnected-(S3-PadO)") (class "Default")
      (node (ref "S3") (pin "O") (pinfunction "O_O") (pintype "passive"))
    )
    (net (code "56") (name "unconnected-(U5-DE-PadP$38)") (class "Default")
      (node (ref "U5") (pin "P$38") (pinfunction "DE_P$38") (pintype "bidirectional"))
    )
    (net (code "57") (name "unconnected-(U5-DSI_CLKN-PadP$36)") (class "Default")
      (node (ref "U5") (pin "P$36") (pinfunction "DSI_CLKN_P$36") (pintype "bidirectional"))
    )
    (net (code "58") (name "unconnected-(U5-DSI_CLKP-PadP$37)") (class "Default")
      (node (ref "U5") (pin "P$37") (pinfunction "DSI_CLKP_P$37") (pintype "bidirectional"))
    )
    (net (code "59") (name "unconnected-(U5-DSI_DON-PadP$34)") (class "Default")
      (node (ref "U5") (pin "P$34") (pinfunction "DSI_DON_P$34") (pintype "bidirectional"))
    )
    (net (code "60") (name "unconnected-(U5-DSI_DOP-PadP$35)") (class "Default")
      (node (ref "U5") (pin "P$35") (pinfunction "DSI_DOP_P$35") (pintype "bidirectional"))
    )
    (net (code "61") (name "unconnected-(U5-DSI_VCC-PadP$33)") (class "Default")
      (node (ref "U5") (pin "P$33") (pinfunction "DSI_VCC_P$33") (pintype "bidirectional"))
    )
    (net (code "62") (name "unconnected-(U5-FMARK-PadP$9)") (class "Default")
      (node (ref "U5") (pin "P$9") (pinfunction "FMARK_P$9") (pintype "bidirectional"))
    )
    (net (code "63") (name "unconnected-(U5-HSYNC-PadP$40)") (class "Default")
      (node (ref "U5") (pin "P$40") (pinfunction "HSYNC_P$40") (pintype "bidirectional"))
    )
    (net (code "64") (name "unconnected-(U5-PCLK-PadP$39)") (class "Default")
      (node (ref "U5") (pin "P$39") (pinfunction "PCLK_P$39") (pintype "bidirectional"))
    )
    (net (code "65") (name "unconnected-(U5-PWM_OUT-PadP$8)") (class "Default")
      (node (ref "U5") (pin "P$8") (pinfunction "PWM_OUT_P$8") (pintype "bidirectional"))
    )
    (net (code "66") (name "unconnected-(U5-RDX-PadP$32)") (class "Default")
      (node (ref "U5") (pin "P$32") (pinfunction "RDX_P$32") (pintype "bidirectional"))
    )
    (net (code "67") (name "unconnected-(U5-VSYNC-PadP$41)") (class "Default")
      (node (ref "U5") (pin "P$41") (pinfunction "VSYNC_P$41") (pintype "bidirectional"))
    )
    (net (code "68") (name "unconnected-(U5-XL-PadP$2)") (class "Default")
      (node (ref "U5") (pin "P$2") (pinfunction "XL_P$2") (pintype "bidirectional"))
    )
    (net (code "69") (name "unconnected-(U5-XR-PadP$4)") (class "Default")
      (node (ref "U5") (pin "P$4") (pinfunction "XR_P$4") (pintype "bidirectional"))
    )
    (net (code "70") (name "unconnected-(U5-YD-PadP$3)") (class "Default")
      (node (ref "U5") (pin "P$3") (pinfunction "YD_P$3") (pintype "bidirectional"))
    )
    (net (code "71") (name "unconnected-(U5-YU-PadP$1)") (class "Default")
      (node (ref "U5") (pin "P$1") (pinfunction "YU_P$1") (pintype "bidirectional"))
    )
  )
)
